# STM32.net
KiCad netlist of a schematic drawn in Altium Designer
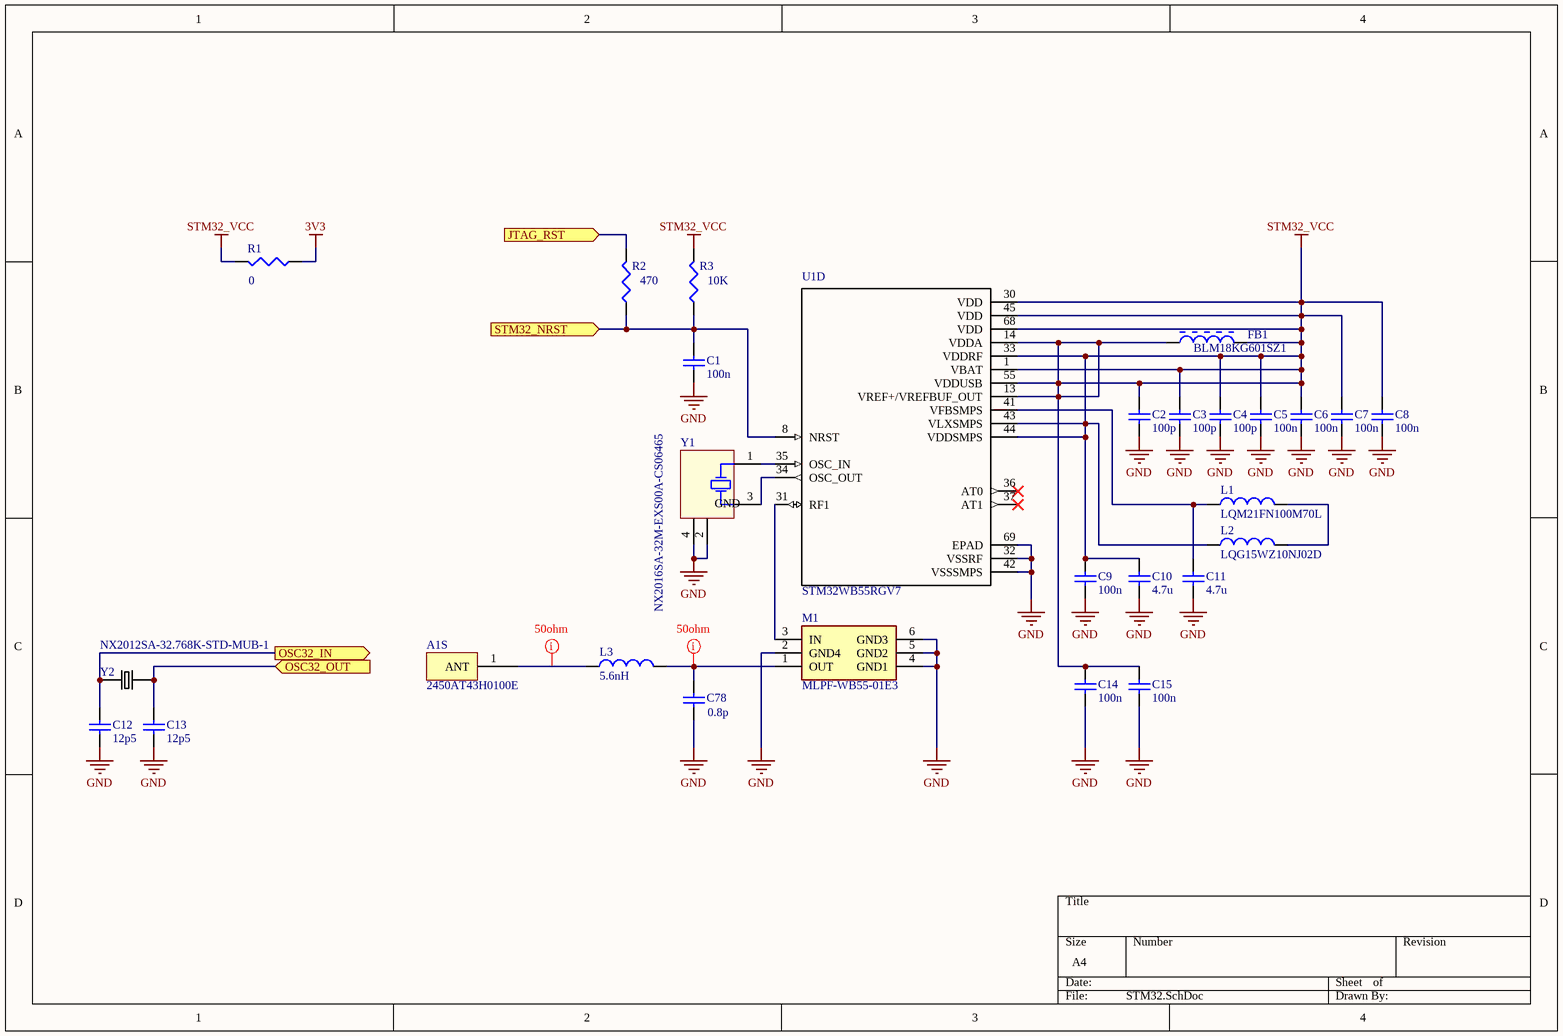
[diagram p0: STM32.SchDoc]

(export (version "E")
  (design (tool "Eeschema 10.0.6"))
  (components
    (comp (ref "A1S")
      (value "2450AT43H0100E")
      (footprint "2450AT43H0100E")
      (libsource (lib "STM32WB55RGV7") (part "2450AT43H0100E"))
    )
    (comp (ref "C1")
      (value "100n")
      (footprint "CAPC1608X90X35NL10T15")
      (fields (field (name "PART NUMBER") "GRM188R71H102KA01D") (field (name "MANUFACTURER") "Murata"))
      (libsource (lib "Altium Content Vault") (part "CAP"))
    )
    (comp (ref "C2")
      (value "100p")
      (footprint "CAPC1608X90X35NL10T15")
      (libsource (lib "Altium Content Vault") (part "CAP"))
    )
    (comp (ref "C3")
      (value "100p")
      (footprint "CAPC1608X90X35NL10T15")
      (libsource (lib "Altium Content Vault") (part "CAP"))
    )
    (comp (ref "C4")
      (value "100p")
      (footprint "CAPC1608X90X35NL10T15")
      (libsource (lib "Altium Content Vault") (part "CAP"))
    )
    (comp (ref "C5")
      (value "100n")
      (footprint "CAPC1608X90X35NL10T15")
      (libsource (lib "Altium Content Vault") (part "CAP"))
    )
    (comp (ref "C6")
      (value "100n")
      (footprint "CAPC1608X90X35NL10T15")
      (libsource (lib "Altium Content Vault") (part "CAP"))
    )
    (comp (ref "C7")
      (value "100n")
      (footprint "CAPC1608X90X35NL10T15")
      (libsource (lib "Altium Content Vault") (part "CAP"))
    )
    (comp (ref "C8")
      (value "100n")
      (footprint "CAPC1608X90X35NL10T15")
      (libsource (lib "Altium Content Vault") (part "CAP"))
    )
    (comp (ref "C9")
      (value "100n")
      (footprint "CAPC1608X90X35NL10T15")
      (libsource (lib "Altium Content Vault") (part "CAP"))
    )
    (comp (ref "C10")
      (value "4.7u")
      (footprint "CAPC1608X90X35NL10T15")
      (libsource (lib "Altium Content Vault") (part "CAP"))
    )
    (comp (ref "C11")
      (value "4.7u")
      (footprint "CAPC1608X90X35NL10T15")
      (libsource (lib "Altium Content Vault") (part "CAP"))
    )
    (comp (ref "C12")
      (value "12p5")
      (footprint "CAPC1608X90X35NL10T15")
      (libsource (lib "Altium Content Vault") (part "CAP"))
    )
    (comp (ref "C13")
      (value "12p5")
      (footprint "CAPC1608X90X35NL10T15")
      (libsource (lib "Altium Content Vault") (part "CAP"))
    )
    (comp (ref "C14")
      (value "100n")
      (footprint "CAPC1608X90X35NL10T15")
      (libsource (lib "Altium Content Vault") (part "CAP"))
    )
    (comp (ref "C15")
      (value "100n")
      (footprint "CAPC1608X90X35NL10T15")
      (fields (field (name "PART NUMBER") "GRM188R71H102KA01D") (field (name "MANUFACTURER") "Murata"))
      (libsource (lib "Altium Content Vault") (part "CAP"))
    )
    (comp (ref "C78")
      (value "0.8p")
      (footprint "CAPC1005X55X25ML05T10")
      (libsource (lib "Altium Content Vault") (part "CAP"))
    )
    (comp (ref "FB1")
      (value "BLM18KG601SZ1")
      (footprint "MURA-BLM18SG-B25-CHIP-2_V1")
      (fields (field (name "MANUFACTURER") "Murata") (field (name "PARTNUMBER") "BLM18SG221TN1D"))
      (libsource (lib "Altium Content Vault") (part "MURA-FB-2"))
    )
    (comp (ref "L1")
      (value "LQM21FN100M70L")
      (footprint "MURA-IND0805_L")
      (description "Fixed Inductor, 10 uH, +/-20%, -55 to 125 degC, 2-Pin SMD (0805), RoHS, Tape and Reel")
      (fields (field (name "MANUFACTURER") "Murata"))
      (libsource (lib "Altium Content Vault") (part "IND-2"))
    )
    (comp (ref "L2")
      (value "LQG15WZ10NJ02D")
      (footprint "0402-A")
      (description "Inductor")
      (fields (field (name "PUBLISHER") "Altium Limited"))
      (libsource (lib "Miscellaneous Devices") (part "Inductor"))
    )
    (comp (ref "L3")
      (value "5.6nH")
      (footprint "0402-A")
      (description "Inductor")
      (fields (field (name "PUBLISHER") "Altium Limited"))
      (libsource (lib "Miscellaneous Devices") (part "Inductor"))
    )
    (comp (ref "M1")
      (value "MLPF-WB55-01E3")
      (footprint "SamacSys:MLPFWB5501E3")
      (description "Filter")
      (fields (field (name "MOUSER PART NUMBER") "511-MLPF-WB55-01E3"))
      (libsource (lib "*") (part "MLPF-WB55-01E3"))
    )
    (comp (ref "R1")
      (value "0")
      (footprint "J1-0603")
      (description "Resistor")
      (fields (field (name "PUBLISHER") "Altium Limited"))
      (libsource (lib "Miscellaneous Devices") (part "Res3"))
    )
    (comp (ref "R2")
      (value "470")
      (footprint "J1-0603")
      (description "Resistor")
      (fields (field (name "PUBLISHER") "Altium Limited"))
      (libsource (lib "Miscellaneous Devices") (part "Res3"))
    )
    (comp (ref "R3")
      (value "10K")
      (footprint "J1-0603")
      (description "Resistor")
      (fields (field (name "PUBLISHER") "Altium Limited"))
      (libsource (lib "Miscellaneous Devices") (part "Res3"))
    )
    (comp (ref "U1")
      (value "STM32WB55RGV7")
      (footprint "*QFN40P800X800X100-69N")
      (description "Multiprotocol wireless 32-bit MCU Arm-based Cortex-M4")
      (fields (field (name "MF") "STMicroelectronics"))
      (libsource (lib "STM32WB55RGV7") (part "STM32WB55RGV7"))
    )
    (comp (ref "Y1")
      (value "NX2016SA-32M-EXS00A-CS06465")
      (footprint "NDK-NX2016SA-26MHZ-EXS00A-CS06025-4_V")
      (description "Crystal, 26 MHz, 8 pF, for OA / AV / Short-range Wireless, -10 to 75 degC, 2.0 x 1.6 x 0.45 mm SMD")
      (fields (field (name "PARTNUMBER") "NX2016SA-26MHZ-EXS00A-CS06025") (field (name "MANUFACTURER") "NDK"))
      (libsource (lib "Altium Content Vault") (part "NDK-NX2016SA-26MHZ-EXS00A-CS06025-4"))
    )
    (comp (ref "Y2")
      (value "NX2012SA-32.768K-STD-MUB-1")
      (footprint "*XTAL_NX2012SA-32.768K-STD-MUB-1")
      (description "Crystal 32.7680khz 12.5pf Smd")
      (fields (field (name "MF") "NDK America,"))
      (libsource (lib "NX2012SA-32.768K-STD-MUB-1") (part "NX2012SA-32.768K-STD-MUB-1"))
    )
  )
  (nets
    (net (code "1") (name "/JTAG_RST") (class "Default")
      (node (ref "R2") (pin "2") (pinfunction "2_2") (pintype "passive"))
    )
    (net (code "2") (name "/OSC32_IN") (class "Default")
      (node (ref "C12") (pin "2") (pinfunction "2_2") (pintype "passive"))
      (node (ref "Y2") (pin "1") (pinfunction "1_1") (pintype "passive"))
    )
    (net (code "3") (name "/OSC32_OUT") (class "Default")
      (node (ref "C13") (pin "2") (pinfunction "2_2") (pintype "passive"))
      (node (ref "Y2") (pin "2") (pinfunction "2_2") (pintype "passive"))
    )
    (net (code "4") (name "/STM32_NRST") (class "Default")
      (node (ref "C1") (pin "2") (pinfunction "2_2") (pintype "passive"))
      (node (ref "R2") (pin "1") (pinfunction "1_1") (pintype "passive"))
      (node (ref "R3") (pin "1") (pinfunction "1_1") (pintype "passive"))
      (node (ref "U1") (pin "8") (pinfunction "NRST_8") (pintype "input"))
    )
    (net (code "5") (name "3V3") (class "Default")
      (node (ref "R1") (pin "1") (pinfunction "1_1") (pintype "passive"))
    )
    (net (code "6") (name "GND") (class "Default")
      (node (ref "C1") (pin "1") (pinfunction "1_1") (pintype "passive"))
      (node (ref "C10") (pin "1") (pinfunction "1_1") (pintype "passive"))
      (node (ref "C11") (pin "1") (pinfunction "1_1") (pintype "passive"))
      (node (ref "C12") (pin "1") (pinfunction "1_1") (pintype "passive"))
      (node (ref "C13") (pin "1") (pinfunction "1_1") (pintype "passive"))
      (node (ref "C14") (pin "1") (pinfunction "1_1") (pintype "passive"))
      (node (ref "C15") (pin "1") (pinfunction "1_1") (pintype "passive"))
      (node (ref "C2") (pin "1") (pinfunction "1_1") (pintype "passive"))
      (node (ref "C3") (pin "1") (pinfunction "1_1") (pintype "passive"))
      (node (ref "C4") (pin "1") (pinfunction "1_1") (pintype "passive"))
      (node (ref "C5") (pin "1") (pinfunction "1_1") (pintype "passive"))
      (node (ref "C6") (pin "1") (pinfunction "1_1") (pintype "passive"))
      (node (ref "C7") (pin "1") (pinfunction "1_1") (pintype "passive"))
      (node (ref "C78") (pin "1") (pinfunction "1_1") (pintype "passive"))
      (node (ref "C8") (pin "1") (pinfunction "1_1") (pintype "passive"))
      (node (ref "C9") (pin "1") (pinfunction "1_1") (pintype "passive"))
      (node (ref "M1") (pin "2") (pinfunction "GND4_2") (pintype "passive"))
      (node (ref "M1") (pin "4") (pinfunction "GND1_4") (pintype "passive"))
      (node (ref "M1") (pin "5") (pinfunction "GND2_5") (pintype "passive"))
      (node (ref "M1") (pin "6") (pinfunction "GND3_6") (pintype "passive"))
      (node (ref "U1") (pin "32") (pinfunction "VSSRF_32") (pintype "power_in"))
      (node (ref "U1") (pin "42") (pinfunction "VSSSMPS_42") (pintype "power_in"))
      (node (ref "U1") (pin "69") (pinfunction "EPAD_69") (pintype "power_in"))
      (node (ref "Y1") (pin "2") (pinfunction "GND_2") (pintype "power_in"))
      (node (ref "Y1") (pin "4") (pinfunction "GND_4") (pintype "power_in"))
    )
    (net (code "7") (name "Net-(A1S-ANT)") (class "Default")
      (node (ref "A1S") (pin "1") (pinfunction "ANT_1") (pintype "passive"))
      (node (ref "L3") (pin "1") (pinfunction "1_1") (pintype "passive"))
    )
    (net (code "8") (name "Net-(L1-Pad2)") (class "Default")
      (node (ref "L1") (pin "2") (pinfunction "2_2") (pintype "passive"))
      (node (ref "L2") (pin "2") (pinfunction "2_2") (pintype "passive"))
    )
    (net (code "9") (name "Net-(M1-IN)") (class "Default")
      (node (ref "M1") (pin "3") (pinfunction "IN_3") (pintype "passive"))
      (node (ref "U1") (pin "31") (pinfunction "RF1_31") (pintype "bidirectional"))
    )
    (net (code "10") (name "Net-(M1-OUT)") (class "Default")
      (node (ref "C78") (pin "2") (pinfunction "2_2") (pintype "passive"))
      (node (ref "L3") (pin "2") (pinfunction "2_2") (pintype "passive"))
      (node (ref "M1") (pin "1") (pinfunction "OUT_1") (pintype "passive"))
    )
    (net (code "11") (name "Net-(U1D-OSC_IN)") (class "Default")
      (node (ref "U1") (pin "35") (pinfunction "OSC_IN_35") (pintype "input"))
      (node (ref "Y1") (pin "1") (pinfunction "X1_1") (pintype "passive"))
    )
    (net (code "12") (name "Net-(U1D-OSC_OUT)") (class "Default")
      (node (ref "U1") (pin "34") (pinfunction "OSC_OUT_34") (pintype "output"))
      (node (ref "Y1") (pin "3") (pinfunction "X2_3") (pintype "passive"))
    )
    (net (code "13") (name "Net-(U1D-VFBSMPS)") (class "Default")
      (node (ref "C11") (pin "2") (pinfunction "2_2") (pintype "passive"))
      (node (ref "L1") (pin "1") (pinfunction "1_1") (pintype "passive"))
      (node (ref "U1") (pin "41") (pinfunction "VFBSMPS_41") (pintype "power_in"))
    )
    (net (code "14") (name "STM32_VCC") (class "Default")
      (node (ref "C10") (pin "2") (pinfunction "2_2") (pintype "passive"))
      (node (ref "C14") (pin "2") (pinfunction "2_2") (pintype "passive"))
      (node (ref "C15") (pin "2") (pinfunction "2_2") (pintype "passive"))
      (node (ref "C2") (pin "2") (pinfunction "2_2") (pintype "passive"))
      (node (ref "C3") (pin "2") (pinfunction "2_2") (pintype "passive"))
      (node (ref "C4") (pin "2") (pinfunction "2_2") (pintype "passive"))
      (node (ref "C5") (pin "2") (pinfunction "2_2") (pintype "passive"))
      (node (ref "C6") (pin "2") (pinfunction "2_2") (pintype "passive"))
      (node (ref "C7") (pin "2") (pinfunction "2_2") (pintype "passive"))
      (node (ref "C8") (pin "2") (pinfunction "2_2") (pintype "passive"))
      (node (ref "C9") (pin "2") (pinfunction "2_2") (pintype "passive"))
      (node (ref "FB1") (pin "1") (pinfunction "1_1") (pintype "passive"))
      (node (ref "FB1") (pin "2") (pinfunction "2_2") (pintype "passive"))
      (node (ref "L2") (pin "1") (pinfunction "1_1") (pintype "passive"))
      (node (ref "R1") (pin "2") (pinfunction "2_2") (pintype "passive"))
      (node (ref "R3") (pin "2") (pinfunction "2_2") (pintype "passive"))
      (node (ref "U1") (pin "1") (pinfunction "VBAT_1") (pintype "power_in"))
      (node (ref "U1") (pin "13") (pinfunction "VREF+/VREFBUF_OUT_13") (pintype "power_in"))
      (node (ref "U1") (pin "14") (pinfunction "VDDA_14") (pintype "power_in"))
      (node (ref "U1") (pin "30") (pinfunction "VDD_30") (pintype "power_in"))
      (node (ref "U1") (pin "33") (pinfunction "VDDRF_33") (pintype "power_in"))
      (node (ref "U1") (pin "43") (pinfunction "VLXSMPS_43") (pintype "power_in"))
      (node (ref "U1") (pin "44") (pinfunction "VDDSMPS_44") (pintype "power_in"))
      (node (ref "U1") (pin "45") (pinfunction "VDD_45") (pintype "power_in"))
      (node (ref "U1") (pin "55") (pinfunction "VDDUSB_55") (pintype "power_in"))
      (node (ref "U1") (pin "68") (pinfunction "VDD_68") (pintype "power_in"))
    )
    (net (code "15") (name "unconnected-(U1D-AT0-Pad36)") (class "Default")
      (node (ref "U1") (pin "36") (pinfunction "AT0_36") (pintype "output+no_connect"))
    )
    (net (code "16") (name "unconnected-(U1D-AT1-Pad37)") (class "Default")
      (node (ref "U1") (pin "37") (pinfunction "AT1_37") (pintype "output+no_connect"))
    )
  )
)
